# USB_Device.net
KiCad netlist of a schematic drawn in Altium Designer
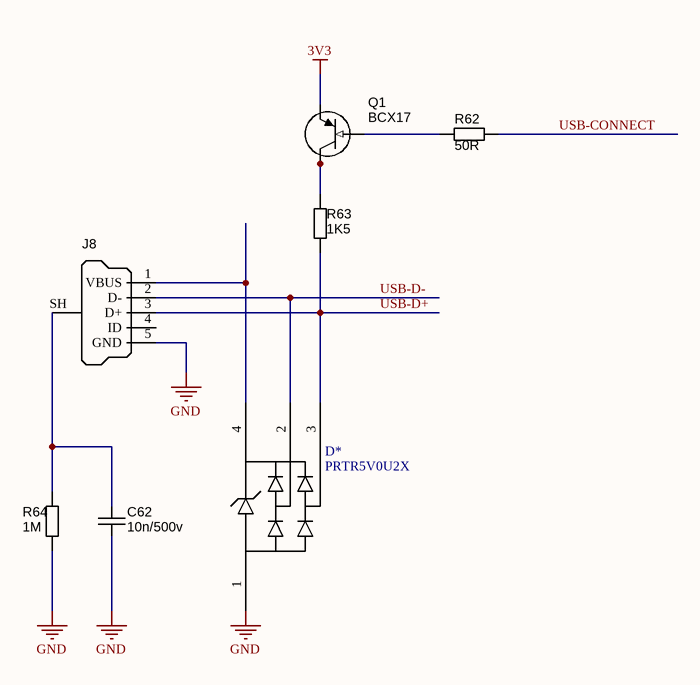
[diagram p0: USB Device.SchDoc]

(export (version "E")
  (design (tool "Eeschema 10.0.6"))
  (components
    (comp (ref "C62")
      (value "10n/500v")
      (footprint "CAPC2012N")
      (description "Capacitor SMD Cer 100nF 10% 50V X7R 0805")
      (fields (field (name "TOLERANCE") "?0%") (field (name "Comment") "approved sub OK"))
      (libsource (lib "PBL - Capacitors") (part "CAPC_100n_0805"))
    )
    (comp (ref "D*") (value "PRTR5V0U2X") (libsource (lib "Schlib1") (part "PRTR5V0U2X")))
    (comp (ref "J8")
      (value "USB Micro Type B")
      (footprint "USB_Micro-B_FCI_SMD")
      (description "Connector SMD-THD USB Micro Type B middle mount")
      (libsource (lib "PBL - Connectors") (part "USB_Micro_TypeB_FCI"))
    )
    (comp (ref "Q1")
      (value "PNP")
      (footprint "SOT23_213")
      (description "Transistor SMD PNP 60V 6A 800mW SOT-223")
      (fields (field (name "MANUFACTURER PART NUMBER 1") "BCX17"))
      (libsource (lib "PBL - Transistors") (part "PNP_NSS60600MZ4T1G"))
    )
    (comp (ref "R62")
      (value "50R")
      (footprint "RESC1005N")
      (description "Resistor SMD chip 330 Ohm 0.063W 5% 0402")
      (fields (field (name "TOLERANCE") "?%") (field (name "Comment") "Thick Film"))
      (libsource (lib "") (part "RES_330R_0402_5%_2"))
    )
    (comp (ref "R63")
      (value "1K5")
      (footprint "RESC1005N")
      (description "Resistor SMD chip 330 Ohm 0.063W 5% 0402")
      (fields (field (name "TOLERANCE") "?%") (field (name "Comment") "Thick Film"))
      (libsource (lib "PBL - Resistors") (part "RES_330R_0402_5%"))
    )
    (comp (ref "R64")
      (value "1M")
      (footprint "RESC1005N")
      (description "Resistor SMD chip 330 Ohm 0.063W 5% 0402")
      (fields (field (name "TOLERANCE") "?%") (field (name "Comment") "Thick Film"))
      (libsource (lib "") (part "RES_330R_0402_5%_1"))
    )
  )
  (nets
    (net (code "1") (name "/USB-CONNECT") (class "Default")
      (node (ref "R62") (pin "1") (pinfunction "1_1") (pintype "passive"))
    )
    (net (code "2") (name "/USB-D+") (class "Default")
      (node (ref "D*") (pin "3") (pinfunction "I/O_2_3") (pintype "passive"))
      (node (ref "J8") (pin "3") (pinfunction "D+_3") (pintype "passive"))
      (node (ref "R63") (pin "2") (pinfunction "2_2") (pintype "passive"))
    )
    (net (code "3") (name "/USB-D-") (class "Default")
      (node (ref "D*") (pin "2") (pinfunction "I/O_1_2") (pintype "passive"))
      (node (ref "J8") (pin "2") (pinfunction "D-_2") (pintype "passive"))
    )
    (net (code "4") (name "3V3") (class "Default")
      (node (ref "Q1") (pin "3") (pinfunction "E_3") (pintype "passive"))
    )
    (net (code "5") (name "GND") (class "Default")
      (node (ref "C62") (pin "2") (pintype "passive"))
      (node (ref "D*") (pin "1") (pinfunction "GND_1") (pintype "passive"))
      (node (ref "J8") (pin "5") (pinfunction "GND_5") (pintype "passive"))
      (node (ref "R64") (pin "1") (pinfunction "1_1") (pintype "passive"))
    )
    (net (code "6") (name "Net-(D*-VCC)") (class "Default")
      (node (ref "D*") (pin "4") (pinfunction "VCC_4") (pintype "passive"))
      (node (ref "J8") (pin "1") (pinfunction "VBUS_1") (pintype "passive"))
    )
    (net (code "7") (name "Net-(J8-Shell)") (class "Default")
      (node (ref "C62") (pin "1") (pintype "passive"))
      (node (ref "J8") (pin "SH") (pinfunction "Shell_SH") (pintype "passive"))
      (node (ref "R64") (pin "2") (pinfunction "2_2") (pintype "passive"))
    )
    (net (code "8") (name "Net-(Q1-B)") (class "Default")
      (node (ref "Q1") (pin "1") (pinfunction "B_1") (pintype "input"))
      (node (ref "R62") (pin "2") (pinfunction "2_2") (pintype "passive"))
    )
    (net (code "9") (name "Net-(Q1-C-Pad2)") (class "Default")
      (node (ref "Q1") (pin "2") (pinfunction "C_2") (pintype "passive"))
      (node (ref "Q1") (pin "4") (pinfunction "C_4") (pintype "passive"))
      (node (ref "R63") (pin "1") (pinfunction "1_1") (pintype "passive"))
    )
    (net (code "10") (name "unconnected-(J8-ID-Pad4)") (class "Default")
      (node (ref "J8") (pin "4") (pinfunction "ID_4") (pintype "passive"))
    )
  )
)
